# LM-008.net
KiCad netlist of a schematic drawn in Altium Designer
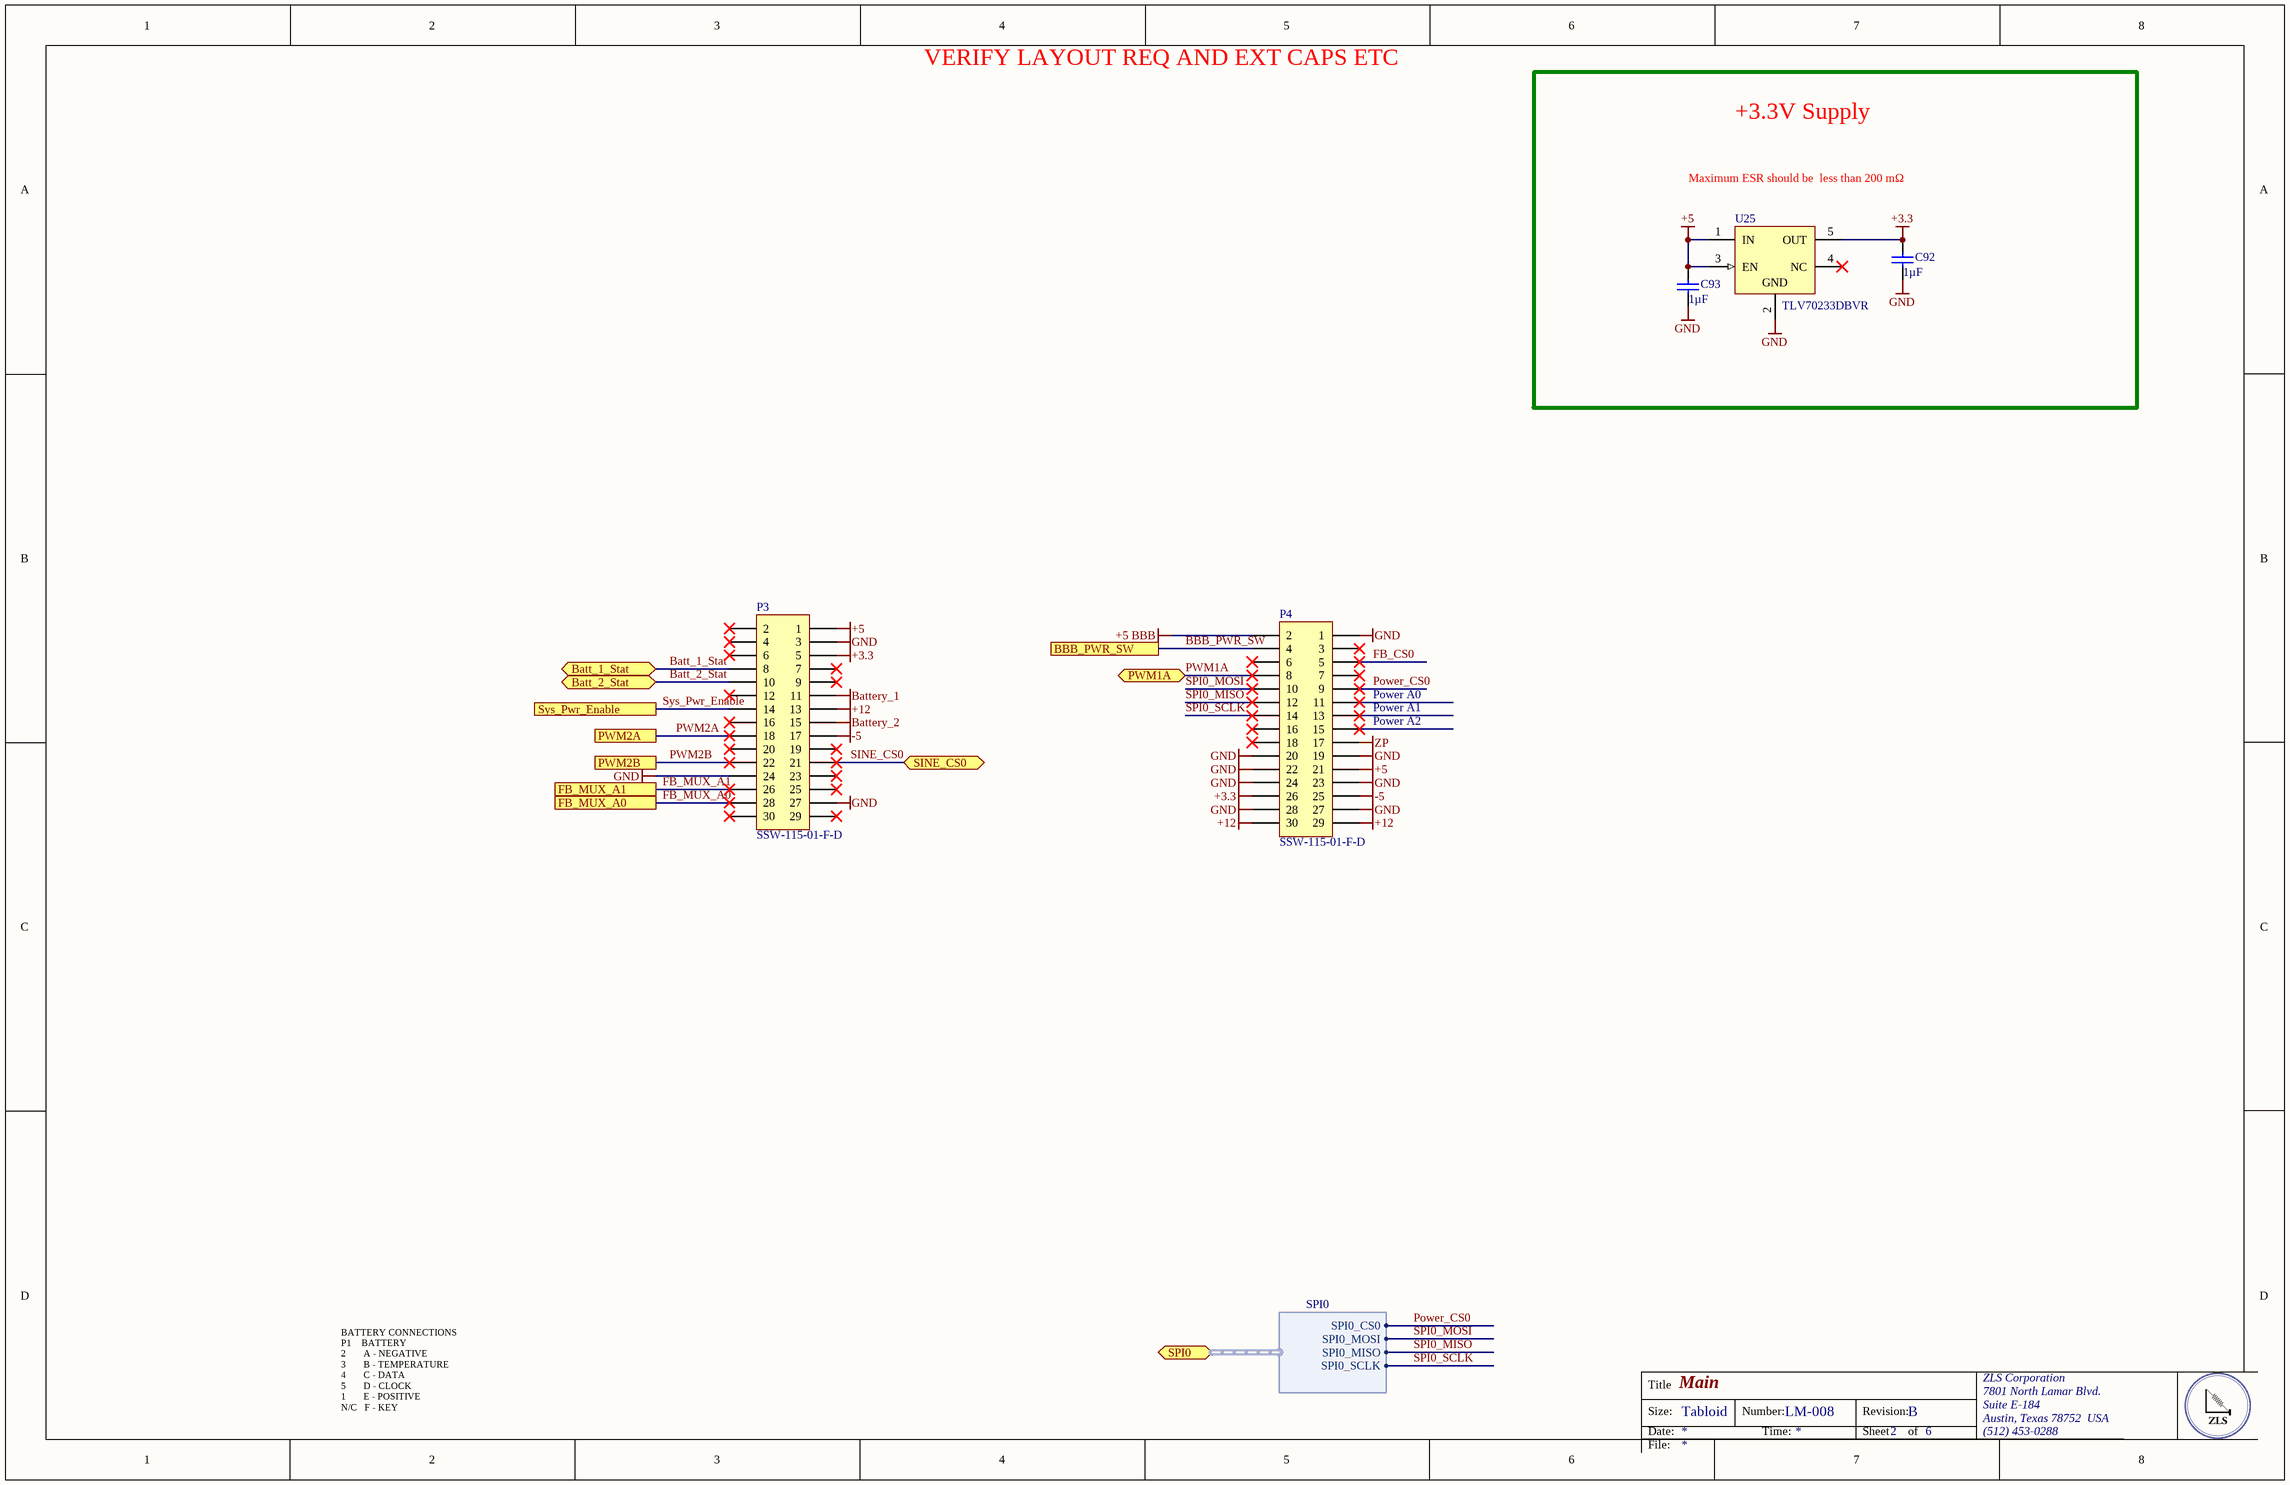
[diagram p0: LM-008.SchDoc]

(export (version "E")
  (design (tool "Eeschema 10.0.6"))
  (components
    (comp (ref "C92")
      (value "CAP CER 1UF 50V X7R 1210")
      (footprint "CAPC1206(3216)130_N")
      (fields
        (field (name "MANUFACTURER") "Murata Electronics North America")
        (field (name "MANUFACTURER PART NUMBER") "GRM32RR71H105KA01L")
        (field (name "CAPACITANCE") "1µF")
        (field (name "TOLERANCE") "±10%")
      )
      (libsource (lib "Altium Content Vault") (part "CMP-1037-04913-1"))
    )
    (comp (ref "C93")
      (value "CAP CER 1UF 50V X7R 1210")
      (footprint "CAPC1206(3216)130_N")
      (fields
        (field (name "MANUFACTURER") "Murata Electronics North America")
        (field (name "MANUFACTURER PART NUMBER") "GRM32RR71H105KA01L")
        (field (name "CAPACITANCE") "1µF")
        (field (name "TOLERANCE") "±10%")
      )
      (libsource (lib "Altium Content Vault") (part "CMP-1037-04913-1"))
    )
    (comp (ref "P3")
      (value "SSW-115-01-F-D")
      (footprint "SSW-115-23-G-D")
      (description "Header, 15-Pin, Dual row")
      (fields (field (name "MANUFACTURER") "Samtec Inc."))
      (libsource (lib "Miscellaneous Connectors") (part "Header 15X2"))
    )
    (comp (ref "P4")
      (value "SSW-115-01-F-D")
      (footprint "SSW-115-23-G-D")
      (description "Header, 15-Pin, Dual row")
      (fields (field (name "MANUFACTURER") "Samtec Inc."))
      (libsource (lib "Miscellaneous Connectors") (part "Header 15X2"))
    )
    (comp (ref "U25")
      (value "TLV70233DBVR")
      (footprint "DBV0005A_N")
      (fields (field (name "MANUFACTURER") "Texas Instruments") (field (name "BASE PART NUMBER") "TLV70233"))
      (libsource (lib "Altium Content Vault") (part "CMP-0394-00528-2"))
    )
  )
  (nets
    (net (code "2") (name "+3.3") (class "Default")
      (node (ref "C92") (pin "2") (pinfunction "2_2") (pintype "passive"))
      (node (ref "P3") (pin "5") (pinfunction "5_5") (pintype "passive"))
      (node (ref "P4") (pin "26") (pinfunction "26_26") (pintype "passive"))
      (node (ref "U25") (pin "5") (pinfunction "OUT_5") (pintype "power_in"))
    )
    (net (code "3") (name "+5") (class "Default")
      (node (ref "C93") (pin "2") (pinfunction "2_2") (pintype "passive"))
      (node (ref "P3") (pin "1") (pinfunction "1_1") (pintype "passive"))
      (node (ref "P4") (pin "21") (pinfunction "21_21") (pintype "passive"))
      (node (ref "U25") (pin "1") (pinfunction "IN_1") (pintype "power_in"))
      (node (ref "U25") (pin "3") (pinfunction "EN_3") (pintype "input"))
    )
    (net (code "4") (name "+5 BBB") (class "Default")
      (node (ref "P4") (pin "2") (pinfunction "2_2") (pintype "passive"))
    )
    (net (code "5") (name "+12") (class "Default")
      (node (ref "P3") (pin "13") (pinfunction "13_13") (pintype "passive"))
      (node (ref "P4") (pin "29") (pinfunction "29_29") (pintype "passive"))
      (node (ref "P4") (pin "30") (pinfunction "30_30") (pintype "passive"))
    )
    (net (code "6") (name "-5") (class "Default")
      (node (ref "P3") (pin "17") (pinfunction "17_17") (pintype "passive"))
      (node (ref "P4") (pin "25") (pinfunction "25_25") (pintype "passive"))
    )
    (net (code "7") (name "/BBB_PWR_SW") (class "Default")
      (node (ref "P4") (pin "4") (pinfunction "4_4") (pintype "passive"))
    )
    (net (code "8") (name "/Batt_1_Stat") (class "Default")
      (node (ref "P3") (pin "8") (pinfunction "8_8") (pintype "passive"))
    )
    (net (code "9") (name "/Batt_2_Stat") (class "Default")
      (node (ref "P3") (pin "10") (pinfunction "10_10") (pintype "passive"))
    )
    (net (code "10") (name "/FB_CS0") (class "Default")
      (node (ref "P4") (pin "5") (pinfunction "5_5") (pintype "passive+no_connect"))
    )
    (net (code "11") (name "/FB_MUX_A0") (class "Default")
      (node (ref "P3") (pin "28") (pinfunction "28_28") (pintype "passive+no_connect"))
    )
    (net (code "12") (name "/FB_MUX_A1") (class "Default")
      (node (ref "P3") (pin "26") (pinfunction "26_26") (pintype "passive+no_connect"))
    )
    (net (code "13") (name "/PWM1A") (class "Default")
      (node (ref "P4") (pin "8") (pinfunction "8_8") (pintype "passive+no_connect"))
    )
    (net (code "14") (name "/PWM2A") (class "Default")
      (node (ref "P3") (pin "18") (pinfunction "18_18") (pintype "passive+no_connect"))
    )
    (net (code "15") (name "/PWM2B") (class "Default")
      (node (ref "P3") (pin "22") (pinfunction "22_22") (pintype "passive+no_connect"))
    )
    (net (code "16") (name "/Power_CS0") (class "Default")
      (node (ref "P4") (pin "9") (pinfunction "9_9") (pintype "passive+no_connect"))
    )
    (net (code "17") (name "/SINE_CS0") (class "Default")
      (node (ref "P3") (pin "21") (pinfunction "21_21") (pintype "passive+no_connect"))
    )
    (net (code "18") (name "/SPI0_MISO") (class "Default")
      (node (ref "P4") (pin "12") (pinfunction "12_12") (pintype "passive"))
    )
    (net (code "19") (name "/SPI0_MOSI") (class "Default")
      (node (ref "P4") (pin "10") (pinfunction "10_10") (pintype "passive"))
    )
    (net (code "20") (name "/SPI0_SCLK") (class "Default")
      (node (ref "P4") (pin "14") (pinfunction "14_14") (pintype "passive"))
    )
    (net (code "21") (name "/Sys_Pwr_Enable") (class "Default")
      (node (ref "P3") (pin "14") (pinfunction "14_14") (pintype "passive"))
    )
    (net (code "23") (name "Battery_1") (class "Default")
      (node (ref "P3") (pin "11") (pinfunction "11_11") (pintype "passive"))
    )
    (net (code "24") (name "Battery_2") (class "Default")
      (node (ref "P3") (pin "15") (pinfunction "15_15") (pintype "passive"))
    )
    (net (code "25") (name "GND") (class "Default")
      (node (ref "C92") (pin "1") (pinfunction "1_1") (pintype "passive"))
      (node (ref "C93") (pin "1") (pinfunction "1_1") (pintype "passive"))
      (node (ref "P3") (pin "24") (pinfunction "24_24") (pintype "passive"))
      (node (ref "P3") (pin "27") (pinfunction "27_27") (pintype "passive"))
      (node (ref "P3") (pin "3") (pinfunction "3_3") (pintype "passive"))
      (node (ref "P4") (pin "1") (pinfunction "1_1") (pintype "passive"))
      (node (ref "P4") (pin "19") (pinfunction "19_19") (pintype "passive"))
      (node (ref "P4") (pin "20") (pinfunction "20_20") (pintype "passive"))
      (node (ref "P4") (pin "22") (pinfunction "22_22") (pintype "passive"))
      (node (ref "P4") (pin "23") (pinfunction "23_23") (pintype "passive"))
      (node (ref "P4") (pin "24") (pinfunction "24_24") (pintype "passive"))
      (node (ref "P4") (pin "27") (pinfunction "27_27") (pintype "passive"))
      (node (ref "P4") (pin "28") (pinfunction "28_28") (pintype "passive"))
      (node (ref "U25") (pin "2") (pinfunction "GND_2") (pintype "power_in"))
    )
    (net (code "26") (name "ZP") (class "Default")
      (node (ref "P4") (pin "17") (pinfunction "17_17") (pintype "passive"))
    )
    (net (code "27") (name "unconnected-(P3-Pad2)") (class "Default")
      (node (ref "P3") (pin "2") (pinfunction "2_2") (pintype "passive+no_connect"))
    )
    (net (code "28") (name "unconnected-(P3-Pad4)") (class "Default")
      (node (ref "P3") (pin "4") (pinfunction "4_4") (pintype "passive+no_connect"))
    )
    (net (code "29") (name "unconnected-(P3-Pad6)") (class "Default")
      (node (ref "P3") (pin "6") (pinfunction "6_6") (pintype "passive+no_connect"))
    )
    (net (code "30") (name "unconnected-(P3-Pad7)") (class "Default")
      (node (ref "P3") (pin "7") (pinfunction "7_7") (pintype "passive+no_connect"))
    )
    (net (code "31") (name "unconnected-(P3-Pad9)") (class "Default")
      (node (ref "P3") (pin "9") (pinfunction "9_9") (pintype "passive+no_connect"))
    )
    (net (code "32") (name "unconnected-(P3-Pad12)") (class "Default")
      (node (ref "P3") (pin "12") (pinfunction "12_12") (pintype "passive+no_connect"))
    )
    (net (code "33") (name "unconnected-(P3-Pad16)") (class "Default")
      (node (ref "P3") (pin "16") (pinfunction "16_16") (pintype "passive+no_connect"))
    )
    (net (code "34") (name "unconnected-(P3-Pad19)") (class "Default")
      (node (ref "P3") (pin "19") (pinfunction "19_19") (pintype "passive+no_connect"))
    )
    (net (code "35") (name "unconnected-(P3-Pad20)") (class "Default")
      (node (ref "P3") (pin "20") (pinfunction "20_20") (pintype "passive+no_connect"))
    )
    (net (code "36") (name "unconnected-(P3-Pad23)") (class "Default")
      (node (ref "P3") (pin "23") (pinfunction "23_23") (pintype "passive+no_connect"))
    )
    (net (code "37") (name "unconnected-(P3-Pad25)") (class "Default")
      (node (ref "P3") (pin "25") (pinfunction "25_25") (pintype "passive+no_connect"))
    )
    (net (code "38") (name "unconnected-(P3-Pad29)") (class "Default")
      (node (ref "P3") (pin "29") (pinfunction "29_29") (pintype "passive+no_connect"))
    )
    (net (code "39") (name "unconnected-(P3-Pad30)") (class "Default")
      (node (ref "P3") (pin "30") (pinfunction "30_30") (pintype "passive+no_connect"))
    )
    (net (code "40") (name "unconnected-(P4-Pad3)") (class "Default")
      (node (ref "P4") (pin "3") (pinfunction "3_3") (pintype "passive+no_connect"))
    )
    (net (code "41") (name "unconnected-(P4-Pad6)") (class "Default")
      (node (ref "P4") (pin "6") (pinfunction "6_6") (pintype "passive+no_connect"))
    )
    (net (code "42") (name "unconnected-(P4-Pad7)") (class "Default")
      (node (ref "P4") (pin "7") (pinfunction "7_7") (pintype "passive+no_connect"))
    )
    (net (code "43") (name "unconnected-(P4-Pad11)") (class "Default")
      (node (ref "P4") (pin "11") (pinfunction "11_11") (pintype "passive+no_connect"))
    )
    (net (code "44") (name "unconnected-(P4-Pad13)") (class "Default")
      (node (ref "P4") (pin "13") (pinfunction "13_13") (pintype "passive+no_connect"))
    )
    (net (code "45") (name "unconnected-(P4-Pad15)") (class "Default")
      (node (ref "P4") (pin "15") (pinfunction "15_15") (pintype "passive+no_connect"))
    )
    (net (code "46") (name "unconnected-(P4-Pad16)") (class "Default")
      (node (ref "P4") (pin "16") (pinfunction "16_16") (pintype "passive+no_connect"))
    )
    (net (code "47") (name "unconnected-(P4-Pad18)") (class "Default")
      (node (ref "P4") (pin "18") (pinfunction "18_18") (pintype "passive+no_connect"))
    )
    (net (code "48") (name "unconnected-(U25-NC-Pad4)") (class "Default")
      (node (ref "U25") (pin "4") (pinfunction "NC_4") (pintype "passive+no_connect"))
    )
  )
)
